# Femtoduino.net
KiCad netlist of a schematic drawn in EAGLE
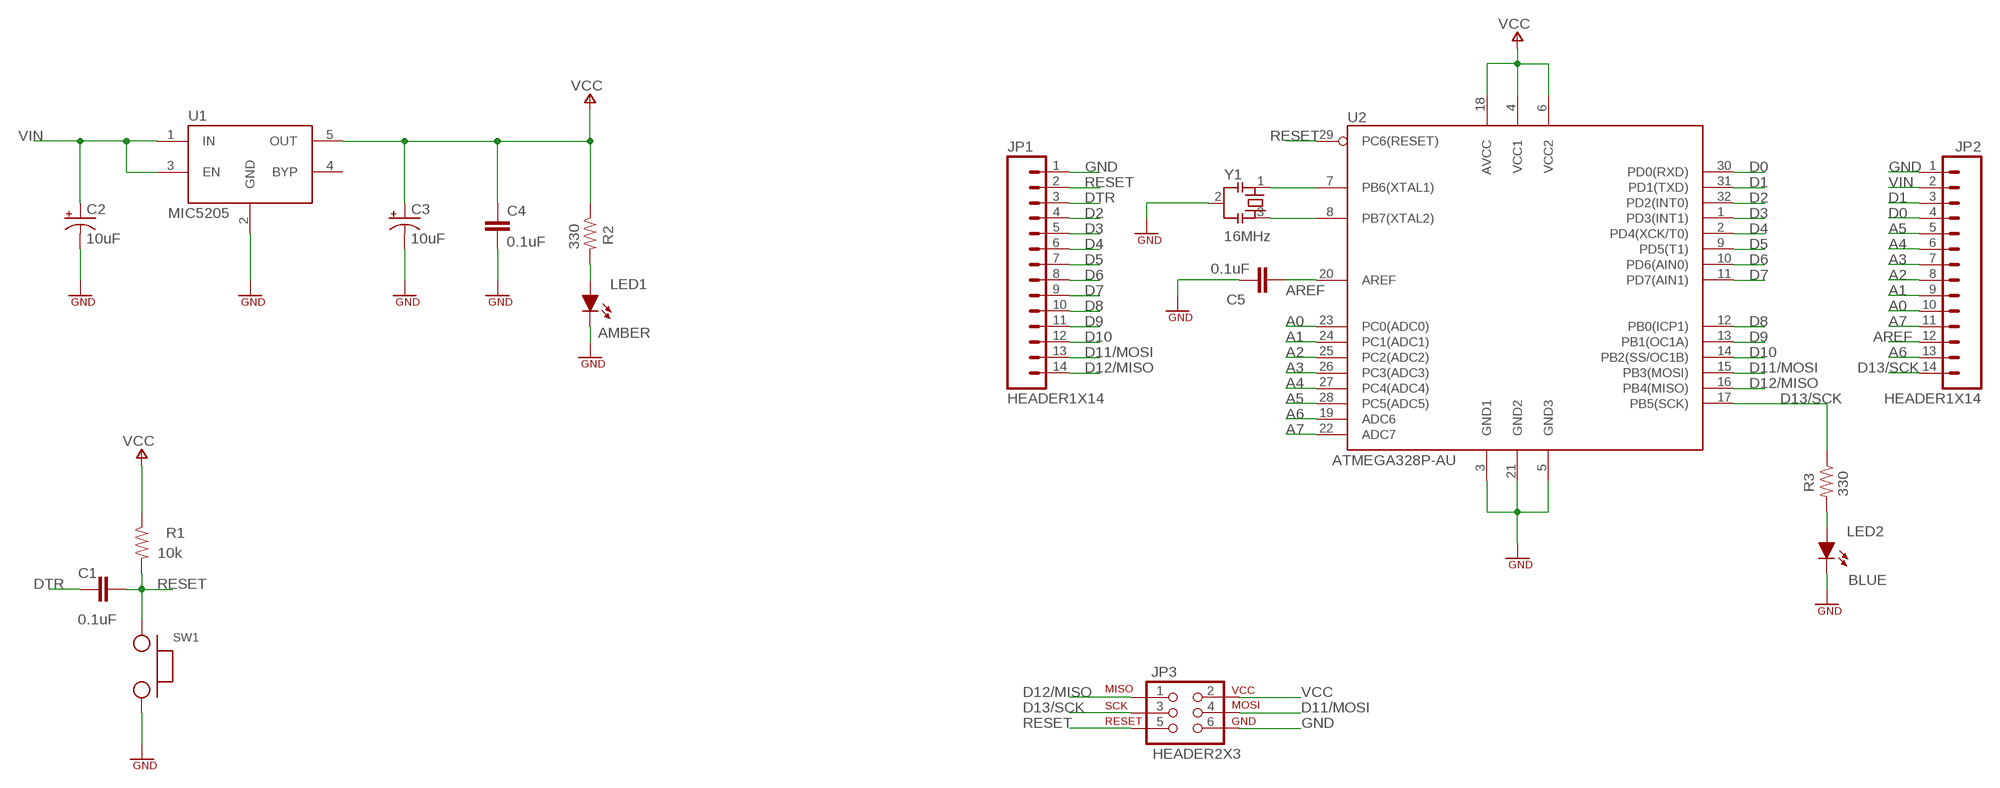
[diagram p0: schematic, sheet 1]

(export (version "E")
  (design (tool "Eeschema 10.0.6"))
  (components
    (comp (ref "C1")
      (value "0.1uF")
      (footprint "eagle-import:SMD0603")
      (libsource (lib "eagle-import") (part "CAP_0603"))
    )
    (comp (ref "C2")
      (value "10uF")
      (footprint "eagle-import:EIA3216")
      (libsource (lib "eagle-import") (part "CAP_TANT"))
    )
    (comp (ref "C3")
      (value "10uF")
      (footprint "eagle-import:EIA3216")
      (libsource (lib "eagle-import") (part "CAP_TANT"))
    )
    (comp (ref "C4")
      (value "0.1uF")
      (footprint "eagle-import:SMD0603")
      (libsource (lib "eagle-import") (part "CAP_0603"))
    )
    (comp (ref "C5")
      (value "0.1uF")
      (footprint "eagle-import:SMD0603")
      (libsource (lib "eagle-import") (part "CAP_0603"))
    )
    (comp (ref "JP1")
      (value "HEADER1X14")
      (footprint "eagle-import:1X14")
      (libsource (lib "eagle-import") (part "HEADER1X14"))
    )
    (comp (ref "JP2")
      (value "HEADER1X14")
      (footprint "eagle-import:1X14")
      (libsource (lib "eagle-import") (part "HEADER1X14"))
    )
    (comp (ref "JP3")
      (value "HEADER2X3")
      (footprint "eagle-import:2X3")
      (libsource (lib "eagle-import") (part "HEADER2X3"))
    )
    (comp (ref "LED1")
      (value "AMBER")
      (footprint "eagle-import:LED_0603")
      (libsource (lib "eagle-import") (part "LED_0603"))
    )
    (comp (ref "LED2")
      (value "BLUE")
      (footprint "eagle-import:LED_0805")
      (libsource (lib "eagle-import") (part "LED_0805"))
    )
    (comp (ref "R1")
      (value "10k")
      (footprint "eagle-import:SMD0603")
      (libsource (lib "eagle-import") (part "RES_0603"))
    )
    (comp (ref "R2")
      (value "330")
      (footprint "eagle-import:SMD0603")
      (libsource (lib "eagle-import") (part "RES_0603"))
    )
    (comp (ref "R3")
      (value "330")
      (footprint "eagle-import:SMD0603")
      (libsource (lib "eagle-import") (part "RES_0603"))
    )
    (comp (ref "SW1")
      (value "SWITCH")
      (footprint "eagle-import:SWITCH-SPST")
      (libsource (lib "eagle-import") (part "SWITCH"))
    )
    (comp (ref "U1")
      (value "MIC5205")
      (footprint "eagle-import:SOT23-5")
      (libsource (lib "eagle-import") (part "MIC5205"))
    )
    (comp (ref "U2")
      (value "ATMEGA328P-AU")
      (footprint "eagle-import:TQFP32")
      (libsource (lib "eagle-import") (part "ATMEGA328P-AU"))
    )
    (comp (ref "Y1")
      (value "16MHz")
      (footprint "eagle-import:CSTCE")
      (libsource (lib "eagle-import") (part "CSTCE"))
    )
  )
  (nets
    (net (code "1") (name "/A0") (class "Default")
      (node (ref "JP2") (pin "10") (pinfunction "10_10") (pintype "passive"))
      (node (ref "U2") (pin "23") (pinfunction "PC0(ADC0)_23") (pintype "bidirectional"))
    )
    (net (code "2") (name "/A1") (class "Default")
      (node (ref "JP2") (pin "9") (pinfunction "9_9") (pintype "passive"))
      (node (ref "U2") (pin "24") (pinfunction "PC1(ADC1)_24") (pintype "bidirectional"))
    )
    (net (code "3") (name "/A2") (class "Default")
      (node (ref "JP2") (pin "8") (pinfunction "8_8") (pintype "passive"))
      (node (ref "U2") (pin "25") (pinfunction "PC2(ADC2)_25") (pintype "bidirectional"))
    )
    (net (code "4") (name "/A3") (class "Default")
      (node (ref "JP2") (pin "7") (pinfunction "7_7") (pintype "passive"))
      (node (ref "U2") (pin "26") (pinfunction "PC3(ADC3)_26") (pintype "bidirectional"))
    )
    (net (code "5") (name "/A4") (class "Default")
      (node (ref "JP2") (pin "6") (pinfunction "6_6") (pintype "passive"))
      (node (ref "U2") (pin "27") (pinfunction "PC4(ADC4)_27") (pintype "bidirectional"))
    )
    (net (code "6") (name "/A5") (class "Default")
      (node (ref "JP2") (pin "5") (pinfunction "5_5") (pintype "passive"))
      (node (ref "U2") (pin "28") (pinfunction "PC5(ADC5)_28") (pintype "bidirectional"))
    )
    (net (code "7") (name "/A6") (class "Default")
      (node (ref "JP2") (pin "13") (pinfunction "13_13") (pintype "passive"))
      (node (ref "U2") (pin "19") (pinfunction "ADC6_19") (pintype "bidirectional"))
    )
    (net (code "8") (name "/A7") (class "Default")
      (node (ref "JP2") (pin "11") (pinfunction "11_11") (pintype "passive"))
      (node (ref "U2") (pin "22") (pinfunction "ADC7_22") (pintype "bidirectional"))
    )
    (net (code "9") (name "/AREF") (class "Default")
      (node (ref "C5") (pin "1") (pinfunction "1_1") (pintype "passive"))
      (node (ref "JP2") (pin "12") (pinfunction "12_12") (pintype "passive"))
      (node (ref "U2") (pin "20") (pinfunction "AREF_20") (pintype "bidirectional"))
    )
    (net (code "10") (name "/D0") (class "Default")
      (node (ref "JP2") (pin "4") (pinfunction "4_4") (pintype "passive"))
      (node (ref "U2") (pin "30") (pinfunction "PD0(RXD)_30") (pintype "bidirectional"))
    )
    (net (code "11") (name "/D1") (class "Default")
      (node (ref "JP2") (pin "3") (pinfunction "3_3") (pintype "passive"))
      (node (ref "U2") (pin "31") (pinfunction "PD1(TXD)_31") (pintype "bidirectional"))
    )
    (net (code "12") (name "/D2") (class "Default")
      (node (ref "JP1") (pin "4") (pinfunction "4_4") (pintype "passive"))
      (node (ref "U2") (pin "32") (pinfunction "PD2(INT0)_32") (pintype "bidirectional"))
    )
    (net (code "13") (name "/D3") (class "Default")
      (node (ref "JP1") (pin "5") (pinfunction "5_5") (pintype "passive"))
      (node (ref "U2") (pin "1") (pinfunction "PD3(INT1)_1") (pintype "bidirectional"))
    )
    (net (code "14") (name "/D4") (class "Default")
      (node (ref "JP1") (pin "6") (pinfunction "6_6") (pintype "passive"))
      (node (ref "U2") (pin "2") (pinfunction "PD4(XCK/T0)_2") (pintype "bidirectional"))
    )
    (net (code "15") (name "/D5") (class "Default")
      (node (ref "JP1") (pin "7") (pinfunction "7_7") (pintype "passive"))
      (node (ref "U2") (pin "9") (pinfunction "PD5(T1)_9") (pintype "bidirectional"))
    )
    (net (code "16") (name "/D6") (class "Default")
      (node (ref "JP1") (pin "8") (pinfunction "8_8") (pintype "passive"))
      (node (ref "U2") (pin "10") (pinfunction "PD6(AIN0)_10") (pintype "bidirectional"))
    )
    (net (code "17") (name "/D7") (class "Default")
      (node (ref "JP1") (pin "9") (pinfunction "9_9") (pintype "passive"))
      (node (ref "U2") (pin "11") (pinfunction "PD7(AIN1)_11") (pintype "bidirectional"))
    )
    (net (code "18") (name "/D8") (class "Default")
      (node (ref "JP1") (pin "10") (pinfunction "10_10") (pintype "passive"))
      (node (ref "U2") (pin "12") (pinfunction "PB0(ICP1)_12") (pintype "bidirectional"))
    )
    (net (code "19") (name "/D9") (class "Default")
      (node (ref "JP1") (pin "11") (pinfunction "11_11") (pintype "passive"))
      (node (ref "U2") (pin "13") (pinfunction "PB1(OC1A)_13") (pintype "bidirectional"))
    )
    (net (code "20") (name "/D10") (class "Default")
      (node (ref "JP1") (pin "12") (pinfunction "12_12") (pintype "passive"))
      (node (ref "U2") (pin "14") (pinfunction "PB2(SS/OC1B)_14") (pintype "bidirectional"))
    )
    (net (code "21") (name "/D11{slash}MOSI") (class "Default")
      (node (ref "JP1") (pin "13") (pinfunction "13_13") (pintype "passive"))
      (node (ref "JP3") (pin "4") (pinfunction "4_4") (pintype "passive"))
      (node (ref "U2") (pin "15") (pinfunction "PB3(MOSI)_15") (pintype "bidirectional"))
    )
    (net (code "22") (name "/D12{slash}MISO") (class "Default")
      (node (ref "JP1") (pin "14") (pinfunction "14_14") (pintype "passive"))
      (node (ref "JP3") (pin "1") (pinfunction "1_1") (pintype "passive"))
      (node (ref "U2") (pin "16") (pinfunction "PB4(MISO)_16") (pintype "bidirectional"))
    )
    (net (code "23") (name "/D13{slash}SCK") (class "Default")
      (node (ref "JP2") (pin "14") (pinfunction "14_14") (pintype "passive"))
      (node (ref "JP3") (pin "3") (pinfunction "3_3") (pintype "passive"))
      (node (ref "R3") (pin "1") (pinfunction "1_1") (pintype "passive"))
      (node (ref "U2") (pin "17") (pinfunction "PB5(SCK)_17") (pintype "bidirectional"))
    )
    (net (code "24") (name "/DTR") (class "Default")
      (node (ref "C1") (pin "1") (pinfunction "1_1") (pintype "passive"))
      (node (ref "JP1") (pin "3") (pinfunction "3_3") (pintype "passive"))
    )
    (net (code "25") (name "/RESET") (class "Default")
      (node (ref "C1") (pin "2") (pinfunction "2_2") (pintype "passive"))
      (node (ref "JP1") (pin "2") (pinfunction "2_2") (pintype "passive"))
      (node (ref "JP3") (pin "5") (pinfunction "5_5") (pintype "passive"))
      (node (ref "R1") (pin "2") (pinfunction "2_2") (pintype "passive"))
      (node (ref "SW1") (pin "1") (pinfunction "1_1") (pintype "bidirectional"))
      (node (ref "U2") (pin "29") (pinfunction "PC6(RESET)_29") (pintype "bidirectional"))
    )
    (net (code "26") (name "/VIN") (class "Default")
      (node (ref "C2") (pin "A") (pinfunction "+_A") (pintype "passive"))
      (node (ref "JP2") (pin "2") (pinfunction "2_2") (pintype "passive"))
      (node (ref "U1") (pin "1") (pinfunction "IN_1") (pintype "bidirectional"))
      (node (ref "U1") (pin "3") (pinfunction "EN_3") (pintype "bidirectional"))
    )
    (net (code "27") (name "GND") (class "Default")
      (node (ref "C2") (pin "C") (pinfunction "-_C") (pintype "passive"))
      (node (ref "C3") (pin "C") (pinfunction "-_C") (pintype "passive"))
      (node (ref "C4") (pin "2") (pinfunction "2_2") (pintype "passive"))
      (node (ref "C5") (pin "2") (pinfunction "2_2") (pintype "passive"))
      (node (ref "JP1") (pin "1") (pinfunction "1_1") (pintype "passive"))
      (node (ref "JP2") (pin "1") (pinfunction "1_1") (pintype "passive"))
      (node (ref "JP3") (pin "6") (pinfunction "6_6") (pintype "passive"))
      (node (ref "LED1") (pin "C") (pinfunction "C_C") (pintype "passive"))
      (node (ref "LED2") (pin "C") (pinfunction "C_C") (pintype "passive"))
      (node (ref "SW1") (pin "2") (pinfunction "2_2") (pintype "bidirectional"))
      (node (ref "U1") (pin "2") (pinfunction "GND_2") (pintype "bidirectional"))
      (node (ref "U2") (pin "21") (pinfunction "GND2_21") (pintype "bidirectional"))
      (node (ref "U2") (pin "3") (pinfunction "GND1_3") (pintype "bidirectional"))
      (node (ref "U2") (pin "5") (pinfunction "GND3_5") (pintype "bidirectional"))
      (node (ref "Y1") (pin "2") (pinfunction "2_2") (pintype "passive"))
    )
    (net (code "28") (name "Net-(LED1-PadA)") (class "Default")
      (node (ref "LED1") (pin "A") (pinfunction "A_A") (pintype "passive"))
      (node (ref "R2") (pin "2") (pinfunction "2_2") (pintype "passive"))
    )
    (net (code "29") (name "Net-(LED2-PadA)") (class "Default")
      (node (ref "LED2") (pin "A") (pinfunction "A_A") (pintype "passive"))
      (node (ref "R3") (pin "2") (pinfunction "2_2") (pintype "passive"))
    )
    (net (code "30") (name "Net-(U2-PB6(XTAL1))") (class "Default")
      (node (ref "U2") (pin "7") (pinfunction "PB6(XTAL1)_7") (pintype "bidirectional"))
      (node (ref "Y1") (pin "1") (pinfunction "1_1") (pintype "passive"))
    )
    (net (code "31") (name "Net-(U2-PB7(XTAL2))") (class "Default")
      (node (ref "U2") (pin "8") (pinfunction "PB7(XTAL2)_8") (pintype "bidirectional"))
      (node (ref "Y1") (pin "3") (pinfunction "3_3") (pintype "passive"))
    )
    (net (code "32") (name "VCC") (class "Default")
      (node (ref "C3") (pin "A") (pinfunction "+_A") (pintype "passive"))
      (node (ref "C4") (pin "1") (pinfunction "1_1") (pintype "passive"))
      (node (ref "JP3") (pin "2") (pinfunction "2_2") (pintype "passive"))
      (node (ref "R1") (pin "1") (pinfunction "1_1") (pintype "passive"))
      (node (ref "R2") (pin "1") (pinfunction "1_1") (pintype "passive"))
      (node (ref "U1") (pin "5") (pinfunction "OUT_5") (pintype "bidirectional"))
      (node (ref "U2") (pin "18") (pinfunction "AVCC_18") (pintype "bidirectional"))
      (node (ref "U2") (pin "4") (pinfunction "VCC1_4") (pintype "bidirectional"))
      (node (ref "U2") (pin "6") (pinfunction "VCC2_6") (pintype "bidirectional"))
    )
    (net (code "33") (name "unconnected-(U1-BYP-Pad4)") (class "Default")
      (node (ref "U1") (pin "4") (pinfunction "BYP_4") (pintype "passive"))
    )
  )
)
